# MCU025A_Connectors.net
KiCad netlist of a schematic drawn in Altium Designer
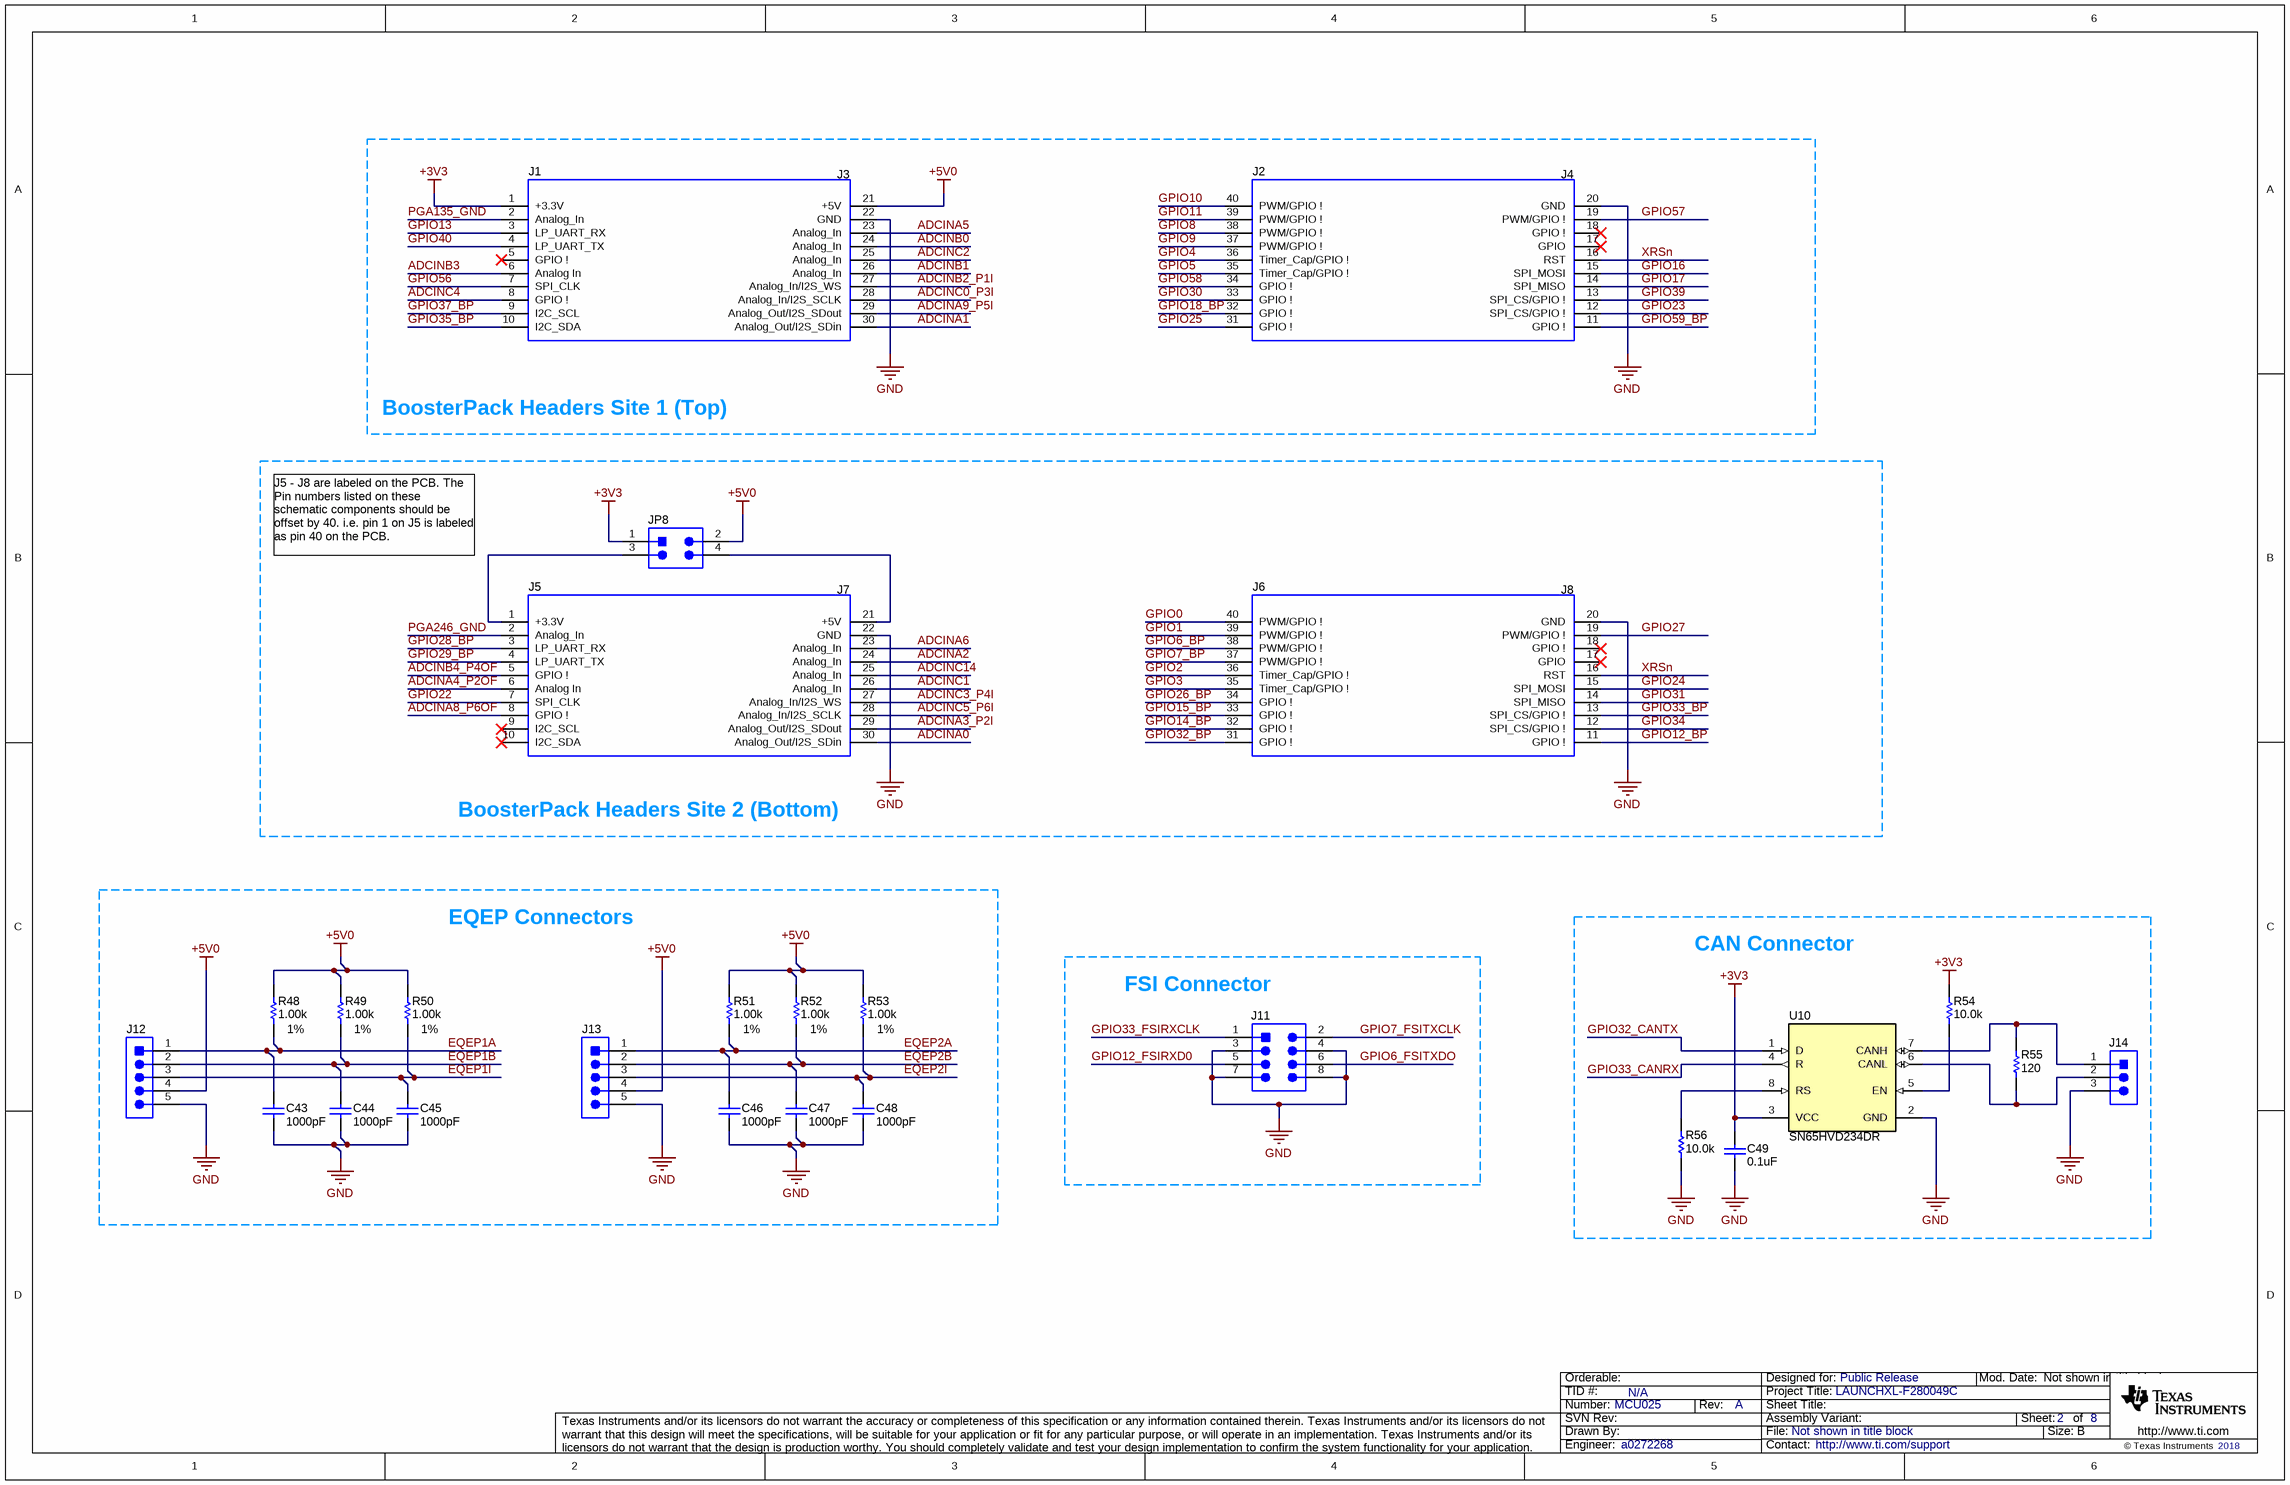
[diagram p0: MCU025A_Connectors.SchDoc]

(export (version "E")
  (design (tool "Eeschema 10.0.6"))
  (components
    (comp (ref "C43")
      (value "GRM155R71H102KA01D")
      (footprint "0402")
      (description "CAP, CERM, 1000 pF, 50 V, +/- 10%, X7R, 0402")
      (fields
        (field (name "VALUEDISPLAYED") "1000pF")
        (field (name "MANUFACTURER") "MuRata")
        (field (name "PUBLISHER") "Texas Instruments")
      )
      (libsource (lib "Altium Vault - TI") (part "Capacitor"))
    )
    (comp (ref "C44")
      (value "GRM155R71H102KA01D")
      (footprint "0402")
      (description "CAP, CERM, 1000 pF, 50 V, +/- 10%, X7R, 0402")
      (fields
        (field (name "VALUEDISPLAYED") "1000pF")
        (field (name "MANUFACTURER") "MuRata")
        (field (name "PUBLISHER") "Texas Instruments")
      )
      (libsource (lib "Altium Vault - TI") (part "Capacitor"))
    )
    (comp (ref "C45")
      (value "GRM155R71H102KA01D")
      (footprint "0402")
      (description "CAP, CERM, 1000 pF, 50 V, +/- 10%, X7R, 0402")
      (fields
        (field (name "VALUEDISPLAYED") "1000pF")
        (field (name "MANUFACTURER") "MuRata")
        (field (name "PUBLISHER") "Texas Instruments")
      )
      (libsource (lib "Altium Vault - TI") (part "Capacitor"))
    )
    (comp (ref "C46")
      (value "GRM155R71H102KA01D")
      (footprint "0402")
      (description "CAP, CERM, 1000 pF, 50 V, +/- 10%, X7R, 0402")
      (fields
        (field (name "VALUEDISPLAYED") "1000pF")
        (field (name "MANUFACTURER") "MuRata")
        (field (name "PUBLISHER") "Texas Instruments")
      )
      (libsource (lib "Altium Vault - TI") (part "Capacitor"))
    )
    (comp (ref "C47")
      (value "GRM155R71H102KA01D")
      (footprint "0402")
      (description "CAP, CERM, 1000 pF, 50 V, +/- 10%, X7R, 0402")
      (fields
        (field (name "VALUEDISPLAYED") "1000pF")
        (field (name "MANUFACTURER") "MuRata")
        (field (name "PUBLISHER") "Texas Instruments")
      )
      (libsource (lib "Altium Vault - TI") (part "Capacitor"))
    )
    (comp (ref "C48")
      (value "GRM155R71H102KA01D")
      (footprint "0402")
      (description "CAP, CERM, 1000 pF, 50 V, +/- 10%, X7R, 0402")
      (fields
        (field (name "VALUEDISPLAYED") "1000pF")
        (field (name "MANUFACTURER") "MuRata")
        (field (name "PUBLISHER") "Texas Instruments")
      )
      (libsource (lib "Altium Vault - TI") (part "Capacitor"))
    )
    (comp (ref "C49")
      (value "GRM155R71A104KA01D")
      (footprint "0402")
      (description "CAP, CERM, 0.1 uF, 10 V, +/- 10%, X7R, 0402")
      (fields
        (field (name "VALUEDISPLAYED") "0.1uF")
        (field (name "MANUFACTURER") "MuRata")
        (field (name "PUBLISHER") "Texas Instruments")
      )
      (libsource (lib "Altium Vault - TI") (part "Capacitor"))
    )
    (comp (ref "J1")
      (value "SSQ-110-03-T-D")
      (footprint "BoosterPack_40pin_J1J3")
      (description "Receptacle, 2.54mm, 10x2, Tin, TH")
      (fields (field (name "MANUFACTURER") "Samtec") (field (name "ALTERNATE PARTNUMBER") "CRD-081413-A-G"))
      (libsource (lib "Altium Vault - TI") (part "BoosterPack_40pin_J1J3"))
    )
    (comp (ref "J2")
      (value "SSQ-110-03-T-D")
      (footprint "BoosterPack_40pin_J2J4")
      (description "Receptacle, 2.54mm, 10x2, Tin, TH")
      (fields (field (name "MANUFACTURER") "Samtec") (field (name "ALTERNATE PARTNUMBER") "CRD-081413-A-G"))
      (libsource (lib "Altium Vault - TI") (part "BoosterPack_40pin_J2J4"))
    )
    (comp (ref "J5")
      (value "SSQ-110-03-T-D")
      (footprint "BoosterPack_40pin_J1J3")
      (description "Receptacle, 2.54mm, 10x2, Tin, TH")
      (fields (field (name "MANUFACTURER") "Samtec") (field (name "ALTERNATE PARTNUMBER") "CRD-081413-A-G"))
      (libsource (lib "Altium Vault - TI") (part "BoosterPack_40pin_J1J3"))
    )
    (comp (ref "J6")
      (value "SSQ-110-03-T-D")
      (footprint "BoosterPack_40pin_J2J4")
      (description "Receptacle, 2.54mm, 10x2, Tin, TH")
      (fields (field (name "MANUFACTURER") "Samtec") (field (name "ALTERNATE PARTNUMBER") "CRD-081413-A-G"))
      (libsource (lib "Altium Vault - TI") (part "BoosterPack_40pin_J2J4"))
    )
    (comp (ref "J11")
      (value "TSW-104-07-G-D")
      (footprint "TSW-104-07-G-D")
      (description "Header, 100mil, 4x2, Gold, TH")
      (fields (field (name "MANUFACTURER") "Samtec") (field (name "PUBLISHER") "Texas Instruments"))
      (libsource (lib "Altium Vault - TI") (part "CMP-0075408-1"))
    )
    (comp (ref "J12")
      (value "TSW-105-07-G-S")
      (footprint "TSW-105-07-X-S")
      (description "Header, 100mil, 5x1, Gold, TH")
      (fields (field (name "MANUFACTURER") "Samtec") (field (name "PUBLISHER") "Texas Instruments"))
      (libsource (lib "Altium Vault - TI") (part "Header_5x1"))
    )
    (comp (ref "J13")
      (value "TSW-105-07-G-S")
      (footprint "TSW-105-07-X-S")
      (description "Header, 100mil, 5x1, Gold, TH")
      (fields (field (name "MANUFACTURER") "Samtec") (field (name "PUBLISHER") "Texas Instruments"))
      (libsource (lib "Altium Vault - TI") (part "Header_5x1"))
    )
    (comp (ref "J14")
      (value "61300311121")
      (footprint "WURTH_61300311121")
      (description "Header, 2.54 mm, 3x1, Gold, TH")
      (fields (field (name "MANUFACTURER") "Wurth Elektronik") (field (name "PUBLISHER") "Texas Instruments"))
      (libsource (lib "Altium Vault - TI") (part "CMP-0054796-1"))
    )
    (comp (ref "JP8")
      (value "TSW-102-07-G-D")
      (footprint "TSW-102-07-G-D")
      (description "Header, 100mil, 2x2, Gold, TH")
      (fields (field (name "MANUFACTURER") "Samtec") (field (name "PUBLISHER") "Texas Instruments"))
      (libsource (lib "Altium Vault - TI") (part "Header_2x2"))
    )
    (comp (ref "R48")
      (value "CRCW04021K00FKED")
      (footprint "0402")
      (description "RES, 1.00 k, 1%, 0.063 W, AEC-Q200 Grade 0, 0402")
      (fields
        (field (name "VALUEDISPLAYED") "1.00k")
        (field (name "MANUFACTURER") "Vishay-Dale")
        (field (name "VALUE1") "1%")
      )
      (libsource (lib "Altium Vault - TI") (part "Resistor"))
    )
    (comp (ref "R49")
      (value "CRCW04021K00FKED")
      (footprint "0402")
      (description "RES, 1.00 k, 1%, 0.063 W, AEC-Q200 Grade 0, 0402")
      (fields
        (field (name "VALUEDISPLAYED") "1.00k")
        (field (name "MANUFACTURER") "Vishay-Dale")
        (field (name "VALUE1") "1%")
      )
      (libsource (lib "Altium Vault - TI") (part "Resistor"))
    )
    (comp (ref "R50")
      (value "CRCW04021K00FKED")
      (footprint "0402")
      (description "RES, 1.00 k, 1%, 0.063 W, AEC-Q200 Grade 0, 0402")
      (fields
        (field (name "VALUEDISPLAYED") "1.00k")
        (field (name "MANUFACTURER") "Vishay-Dale")
        (field (name "VALUE1") "1%")
      )
      (libsource (lib "Altium Vault - TI") (part "Resistor"))
    )
    (comp (ref "R51")
      (value "CRCW04021K00FKED")
      (footprint "0402")
      (description "RES, 1.00 k, 1%, 0.063 W, AEC-Q200 Grade 0, 0402")
      (fields
        (field (name "VALUEDISPLAYED") "1.00k")
        (field (name "MANUFACTURER") "Vishay-Dale")
        (field (name "VALUE1") "1%")
      )
      (libsource (lib "Altium Vault - TI") (part "Resistor"))
    )
    (comp (ref "R52")
      (value "CRCW04021K00FKED")
      (footprint "0402")
      (description "RES, 1.00 k, 1%, 0.063 W, AEC-Q200 Grade 0, 0402")
      (fields
        (field (name "VALUEDISPLAYED") "1.00k")
        (field (name "MANUFACTURER") "Vishay-Dale")
        (field (name "VALUE1") "1%")
      )
      (libsource (lib "Altium Vault - TI") (part "Resistor"))
    )
    (comp (ref "R53")
      (value "CRCW04021K00FKED")
      (footprint "0402")
      (description "RES, 1.00 k, 1%, 0.063 W, AEC-Q200 Grade 0, 0402")
      (fields
        (field (name "VALUEDISPLAYED") "1.00k")
        (field (name "MANUFACTURER") "Vishay-Dale")
        (field (name "VALUE1") "1%")
      )
      (libsource (lib "Altium Vault - TI") (part "Resistor"))
    )
    (comp (ref "R54")
      (value "CRCW040210K0FKED")
      (footprint "0402")
      (description "RES, 10.0 k, 1%, 0.063 W, AEC-Q200 Grade 0, 0402")
      (fields (field (name "VALUEDISPLAYED") "10.0k") (field (name "MANUFACTURER") "Vishay-Dale"))
      (libsource (lib "Altium Vault - TI") (part "Resistor"))
    )
    (comp (ref "R55")
      (value "RC0603FR-07120RL")
      (footprint "0603")
      (description "RES, 120, 1%, 0.1 W, 0603")
      (fields
        (field (name "VALUEDISPLAYED") "120")
        (field (name "MANUFACTURER") "Yageo America")
        (field (name "PUBLISHER") "Texas Instruments")
      )
      (libsource (lib "Altium Vault - TI") (part "Resistor"))
    )
    (comp (ref "R56")
      (value "CRCW040210K0FKED")
      (footprint "0402")
      (description "RES, 10.0 k, 1%, 0.063 W, AEC-Q200 Grade 0, 0402")
      (fields (field (name "VALUEDISPLAYED") "10.0k") (field (name "MANUFACTURER") "Vishay-Dale"))
      (libsource (lib "Altium Vault - TI") (part "Resistor"))
    )
    (comp (ref "U10")
      (value "SN65HVD234DR")
      (footprint "D0008A_L")
      (fields (field (name "MANUFACTURER") "Texas Instruments"))
      (libsource (lib "Altium Vault - TI") (part "TI-SN65HVD234-SOIC_D-8"))
    )
  )
  (nets
    (net (code "1") (name "+3V3") (class "Default")
      (node (ref "C49") (pin "2") (pinfunction "2_2") (pintype "passive"))
      (node (ref "J1") (pin "1") (pinfunction "+3.3V_1") (pintype "power_in"))
      (node (ref "JP8") (pin "1") (pinfunction "1_1") (pintype "passive"))
      (node (ref "R54") (pin "2") (pinfunction "2_2") (pintype "passive"))
      (node (ref "U10") (pin "3") (pinfunction "VCC_3") (pintype "power_in"))
    )
    (net (code "2") (name "+5V0") (class "Default")
      (node (ref "J1") (pin "21") (pinfunction "+5V_21") (pintype "power_in"))
      (node (ref "J12") (pin "4") (pinfunction "4_4") (pintype "passive"))
      (node (ref "J13") (pin "4") (pinfunction "4_4") (pintype "passive"))
      (node (ref "JP8") (pin "2") (pinfunction "2_2") (pintype "passive"))
      (node (ref "R48") (pin "2") (pinfunction "2_2") (pintype "passive"))
      (node (ref "R49") (pin "2") (pinfunction "2_2") (pintype "passive"))
      (node (ref "R50") (pin "2") (pinfunction "2_2") (pintype "passive"))
      (node (ref "R51") (pin "2") (pinfunction "2_2") (pintype "passive"))
      (node (ref "R52") (pin "2") (pinfunction "2_2") (pintype "passive"))
      (node (ref "R53") (pin "2") (pinfunction "2_2") (pintype "passive"))
    )
    (net (code "3") (name "/ADCINA0") (class "Default")
      (node (ref "J5") (pin "30") (pinfunction "Analog_Out/I2S_SDin_30") (pintype "passive"))
    )
    (net (code "4") (name "/ADCINA1") (class "Default")
      (node (ref "J1") (pin "30") (pinfunction "Analog_Out/I2S_SDin_30") (pintype "passive"))
    )
    (net (code "5") (name "/ADCINA2") (class "Default")
      (node (ref "J5") (pin "24") (pinfunction "Analog_In_24") (pintype "passive"))
    )
    (net (code "6") (name "/ADCINA3_P2I") (class "Default")
      (node (ref "J5") (pin "29") (pinfunction "Analog_Out/I2S_SDout_29") (pintype "passive"))
    )
    (net (code "7") (name "/ADCINA4_P2OF") (class "Default")
      (node (ref "J5") (pin "6") (pinfunction "Analog_In_6") (pintype "passive"))
    )
    (net (code "8") (name "/ADCINA5") (class "Default")
      (node (ref "J1") (pin "23") (pinfunction "Analog_In_23") (pintype "passive"))
    )
    (net (code "9") (name "/ADCINA6") (class "Default")
      (node (ref "J5") (pin "23") (pinfunction "Analog_In_23") (pintype "passive"))
    )
    (net (code "10") (name "/ADCINA8_P6OF") (class "Default")
      (node (ref "J5") (pin "8") (pinfunction "GPIO_!_8") (pintype "passive"))
    )
    (net (code "11") (name "/ADCINA9_P5I") (class "Default")
      (node (ref "J1") (pin "29") (pinfunction "Analog_Out/I2S_SDout_29") (pintype "passive"))
    )
    (net (code "12") (name "/ADCINB0") (class "Default")
      (node (ref "J1") (pin "24") (pinfunction "Analog_In_24") (pintype "passive"))
    )
    (net (code "13") (name "/ADCINB1") (class "Default")
      (node (ref "J1") (pin "26") (pinfunction "Analog_In_26") (pintype "passive"))
    )
    (net (code "14") (name "/ADCINB2_P1I") (class "Default")
      (node (ref "J1") (pin "27") (pinfunction "Analog_In/I2S_WS_27") (pintype "passive"))
    )
    (net (code "15") (name "/ADCINB3") (class "Default")
      (node (ref "J1") (pin "6") (pinfunction "Analog_In_6") (pintype "passive"))
    )
    (net (code "16") (name "/ADCINB4_P4OF") (class "Default")
      (node (ref "J5") (pin "5") (pinfunction "GPIO_!_5") (pintype "passive"))
    )
    (net (code "17") (name "/ADCINC0_P3I") (class "Default")
      (node (ref "J1") (pin "28") (pinfunction "Analog_In/I2S_SCLK_28") (pintype "passive"))
    )
    (net (code "18") (name "/ADCINC1") (class "Default")
      (node (ref "J5") (pin "26") (pinfunction "Analog_In_26") (pintype "passive"))
    )
    (net (code "19") (name "/ADCINC2") (class "Default")
      (node (ref "J1") (pin "25") (pinfunction "Analog_In_25") (pintype "passive"))
    )
    (net (code "20") (name "/ADCINC3_P4I") (class "Default")
      (node (ref "J5") (pin "27") (pinfunction "Analog_In/I2S_WS_27") (pintype "passive"))
    )
    (net (code "21") (name "/ADCINC4") (class "Default")
      (node (ref "J1") (pin "8") (pinfunction "GPIO_!_8") (pintype "passive"))
    )
    (net (code "22") (name "/ADCINC5_P6I") (class "Default")
      (node (ref "J5") (pin "28") (pinfunction "Analog_In/I2S_SCLK_28") (pintype "passive"))
    )
    (net (code "23") (name "/ADCINC14") (class "Default")
      (node (ref "J5") (pin "25") (pinfunction "Analog_In_25") (pintype "passive"))
    )
    (net (code "24") (name "/EQEP1A") (class "Default")
      (node (ref "C43") (pin "1") (pinfunction "1_1") (pintype "passive"))
      (node (ref "J12") (pin "1") (pinfunction "1_1") (pintype "passive"))
      (node (ref "R48") (pin "1") (pinfunction "1_1") (pintype "passive"))
    )
    (net (code "25") (name "/EQEP1B") (class "Default")
      (node (ref "C44") (pin "1") (pinfunction "1_1") (pintype "passive"))
      (node (ref "J12") (pin "2") (pinfunction "2_2") (pintype "passive"))
      (node (ref "R49") (pin "1") (pinfunction "1_1") (pintype "passive"))
    )
    (net (code "26") (name "/EQEP1I") (class "Default")
      (node (ref "C45") (pin "1") (pinfunction "1_1") (pintype "passive"))
      (node (ref "J12") (pin "3") (pinfunction "3_3") (pintype "passive"))
      (node (ref "R50") (pin "1") (pinfunction "1_1") (pintype "passive"))
    )
    (net (code "27") (name "/EQEP2A") (class "Default")
      (node (ref "C46") (pin "1") (pinfunction "1_1") (pintype "passive"))
      (node (ref "J13") (pin "1") (pinfunction "1_1") (pintype "passive"))
      (node (ref "R51") (pin "1") (pinfunction "1_1") (pintype "passive"))
    )
    (net (code "28") (name "/EQEP2B") (class "Default")
      (node (ref "C47") (pin "1") (pinfunction "1_1") (pintype "passive"))
      (node (ref "J13") (pin "2") (pinfunction "2_2") (pintype "passive"))
      (node (ref "R52") (pin "1") (pinfunction "1_1") (pintype "passive"))
    )
    (net (code "29") (name "/EQEP2I") (class "Default")
      (node (ref "C48") (pin "1") (pinfunction "1_1") (pintype "passive"))
      (node (ref "J13") (pin "3") (pinfunction "3_3") (pintype "passive"))
      (node (ref "R53") (pin "1") (pinfunction "1_1") (pintype "passive"))
    )
    (net (code "30") (name "/GPIO0") (class "Default")
      (node (ref "J6") (pin "40") (pinfunction "PWM/GPIO_!_40") (pintype "passive"))
    )
    (net (code "31") (name "/GPIO1") (class "Default")
      (node (ref "J6") (pin "39") (pinfunction "PWM/GPIO_!_39") (pintype "passive"))
    )
    (net (code "32") (name "/GPIO2") (class "Default")
      (node (ref "J6") (pin "36") (pinfunction "Timer_Cap/GPIO_!_36") (pintype "passive"))
    )
    (net (code "33") (name "/GPIO3") (class "Default")
      (node (ref "J6") (pin "35") (pinfunction "Timer_Cap/GPIO_!_35") (pintype "passive"))
    )
    (net (code "34") (name "/GPIO4") (class "Default")
      (node (ref "J2") (pin "36") (pinfunction "Timer_Cap/GPIO_!_36") (pintype "passive"))
    )
    (net (code "35") (name "/GPIO5") (class "Default")
      (node (ref "J2") (pin "35") (pinfunction "Timer_Cap/GPIO_!_35") (pintype "passive"))
    )
    (net (code "36") (name "/GPIO6_BP") (class "Default")
      (node (ref "J6") (pin "38") (pinfunction "PWM/GPIO_!_38") (pintype "passive"))
    )
    (net (code "37") (name "/GPIO6_FSITXDO") (class "Default")
      (node (ref "J11") (pin "6") (pinfunction "6_6") (pintype "passive"))
    )
    (net (code "38") (name "/GPIO7_BP") (class "Default")
      (node (ref "J6") (pin "37") (pinfunction "PWM/GPIO_!_37") (pintype "passive"))
    )
    (net (code "39") (name "/GPIO7_FSITXCLK") (class "Default")
      (node (ref "J11") (pin "2") (pinfunction "2_2") (pintype "passive"))
    )
    (net (code "40") (name "/GPIO8") (class "Default")
      (node (ref "J2") (pin "38") (pinfunction "PWM/GPIO_!_38") (pintype "passive"))
    )
    (net (code "41") (name "/GPIO9") (class "Default")
      (node (ref "J2") (pin "37") (pinfunction "PWM/GPIO_!_37") (pintype "passive"))
    )
    (net (code "42") (name "/GPIO10") (class "Default")
      (node (ref "J2") (pin "40") (pinfunction "PWM/GPIO_!_40") (pintype "passive"))
    )
    (net (code "43") (name "/GPIO11") (class "Default")
      (node (ref "J2") (pin "39") (pinfunction "PWM/GPIO_!_39") (pintype "passive"))
    )
    (net (code "44") (name "/GPIO12_BP") (class "Default")
      (node (ref "J6") (pin "11") (pinfunction "GPIO_!_11") (pintype "passive"))
    )
    (net (code "45") (name "/GPIO12_FSIRXD0") (class "Default")
      (node (ref "J11") (pin "5") (pinfunction "5_5") (pintype "passive"))
    )
    (net (code "46") (name "/GPIO13") (class "Default")
      (node (ref "J1") (pin "3") (pinfunction "LP_UART_RX_3") (pintype "passive"))
    )
    (net (code "47") (name "/GPIO14_BP") (class "Default")
      (node (ref "J6") (pin "32") (pinfunction "GPIO_!_32") (pintype "passive"))
    )
    (net (code "48") (name "/GPIO15_BP") (class "Default")
      (node (ref "J6") (pin "33") (pinfunction "GPIO_!_33") (pintype "passive"))
    )
    (net (code "49") (name "/GPIO16") (class "Default")
      (node (ref "J2") (pin "15") (pinfunction "SPI_MOSI_15") (pintype "passive"))
    )
    (net (code "50") (name "/GPIO17") (class "Default")
      (node (ref "J2") (pin "14") (pinfunction "SPI_MISO_14") (pintype "passive"))
    )
    (net (code "51") (name "/GPIO18_BP") (class "Default")
      (node (ref "J2") (pin "32") (pinfunction "GPIO_!_32") (pintype "passive"))
    )
    (net (code "52") (name "/GPIO22") (class "Default")
      (node (ref "J5") (pin "7") (pinfunction "SPI_CLK_7") (pintype "passive"))
    )
    (net (code "53") (name "/GPIO23") (class "Default")
      (node (ref "J2") (pin "12") (pinfunction "SPI_CS/GPIO_!_12") (pintype "passive"))
    )
    (net (code "54") (name "/GPIO24") (class "Default")
      (node (ref "J6") (pin "15") (pinfunction "SPI_MOSI_15") (pintype "passive"))
    )
    (net (code "55") (name "/GPIO25") (class "Default")
      (node (ref "J2") (pin "31") (pinfunction "GPIO_!_31") (pintype "passive"))
    )
    (net (code "56") (name "/GPIO26_BP") (class "Default")
      (node (ref "J6") (pin "34") (pinfunction "GPIO_!_34") (pintype "passive"))
    )
    (net (code "57") (name "/GPIO27") (class "Default")
      (node (ref "J6") (pin "19") (pinfunction "PWM/GPIO_!_19") (pintype "passive"))
    )
    (net (code "58") (name "/GPIO28_BP") (class "Default")
      (node (ref "J5") (pin "3") (pinfunction "LP_UART_RX_3") (pintype "passive"))
    )
    (net (code "59") (name "/GPIO29_BP") (class "Default")
      (node (ref "J5") (pin "4") (pinfunction "LP_UART_TX_4") (pintype "passive"))
    )
    (net (code "60") (name "/GPIO30") (class "Default")
      (node (ref "J2") (pin "33") (pinfunction "GPIO_!_33") (pintype "passive"))
    )
    (net (code "61") (name "/GPIO31") (class "Default")
      (node (ref "J6") (pin "14") (pinfunction "SPI_MISO_14") (pintype "passive"))
    )
    (net (code "62") (name "/GPIO32_BP") (class "Default")
      (node (ref "J6") (pin "31") (pinfunction "GPIO_!_31") (pintype "passive"))
    )
    (net (code "63") (name "/GPIO32_CANTX") (class "Default")
      (node (ref "U10") (pin "1") (pinfunction "D_1") (pintype "input"))
    )
    (net (code "64") (name "/GPIO33_BP") (class "Default")
      (node (ref "J6") (pin "13") (pinfunction "SPI_CS/GPIO_!_13") (pintype "passive"))
    )
    (net (code "65") (name "/GPIO33_CANRX") (class "Default")
      (node (ref "U10") (pin "4") (pinfunction "R_4") (pintype "output"))
    )
    (net (code "66") (name "/GPIO33_FSIRXCLK") (class "Default")
      (node (ref "J11") (pin "1") (pinfunction "1_1") (pintype "passive"))
    )
    (net (code "67") (name "/GPIO34") (class "Default")
      (node (ref "J6") (pin "12") (pinfunction "SPI_CS/GPIO_!_12") (pintype "passive"))
    )
    (net (code "68") (name "/GPIO35_BP") (class "Default")
      (node (ref "J1") (pin "10") (pinfunction "I2C_SDA_10") (pintype "passive"))
    )
    (net (code "69") (name "/GPIO37_BP") (class "Default")
      (node (ref "J1") (pin "9") (pinfunction "I2C_SCL_9") (pintype "passive"))
    )
    (net (code "70") (name "/GPIO39") (class "Default")
      (node (ref "J2") (pin "13") (pinfunction "SPI_CS/GPIO_!_13") (pintype "passive"))
    )
    (net (code "71") (name "/GPIO40") (class "Default")
      (node (ref "J1") (pin "4") (pinfunction "LP_UART_TX_4") (pintype "passive"))
    )
    (net (code "72") (name "/GPIO56") (class "Default")
      (node (ref "J1") (pin "7") (pinfunction "SPI_CLK_7") (pintype "passive"))
    )
    (net (code "73") (name "/GPIO57") (class "Default")
      (node (ref "J2") (pin "19") (pinfunction "PWM/GPIO_!_19") (pintype "passive"))
    )
    (net (code "74") (name "/GPIO58") (class "Default")
      (node (ref "J2") (pin "34") (pinfunction "GPIO_!_34") (pintype "passive"))
    )
    (net (code "75") (name "/GPIO59_BP") (class "Default")
      (node (ref "J2") (pin "11") (pinfunction "GPIO_!_11") (pintype "passive"))
    )
    (net (code "76") (name "/PGA135_GND") (class "Default")
      (node (ref "J1") (pin "2") (pinfunction "Analog_In_2") (pintype "passive"))
    )
    (net (code "77") (name "/PGA246_GND") (class "Default")
      (node (ref "J5") (pin "2") (pinfunction "Analog_In_2") (pintype "passive"))
    )
    (net (code "78") (name "/XRSn") (class "Default")
      (node (ref "J2") (pin "16") (pinfunction "RST_16") (pintype "passive"))
      (node (ref "J6") (pin "16") (pinfunction "RST_16") (pintype "passive"))
    )
    (net (code "79") (name "GND") (class "Default")
      (node (ref "C43") (pin "2") (pinfunction "2_2") (pintype "passive"))
      (node (ref "C44") (pin "2") (pinfunction "2_2") (pintype "passive"))
      (node (ref "C45") (pin "2") (pinfunction "2_2") (pintype "passive"))
      (node (ref "C46") (pin "2") (pinfunction "2_2") (pintype "passive"))
      (node (ref "C47") (pin "2") (pinfunction "2_2") (pintype "passive"))
      (node (ref "C48") (pin "2") (pinfunction "2_2") (pintype "passive"))
      (node (ref "C49") (pin "1") (pinfunction "1_1") (pintype "passive"))
      (node (ref "J1") (pin "22") (pinfunction "GND_22") (pintype "power_in"))
      (node (ref "J11") (pin "3") (pinfunction "3_3") (pintype "passive"))
      (node (ref "J11") (pin "4") (pinfunction "4_4") (pintype "passive"))
      (node (ref "J11") (pin "7") (pinfunction "7_7") (pintype "passive"))
      (node (ref "J11") (pin "8") (pinfunction "8_8") (pintype "passive"))
      (node (ref "J12") (pin "5") (pinfunction "5_5") (pintype "passive"))
      (node (ref "J13") (pin "5") (pinfunction "5_5") (pintype "passive"))
      (node (ref "J14") (pin "3") (pinfunction "3_3") (pintype "passive"))
      (node (ref "J2") (pin "20") (pinfunction "GND_20") (pintype "power_in"))
      (node (ref "J5") (pin "22") (pinfunction "GND_22") (pintype "power_in"))
      (node (ref "J6") (pin "20") (pinfunction "GND_20") (pintype "power_in"))
      (node (ref "R56") (pin "1") (pinfunction "1_1") (pintype "passive"))
      (node (ref "U10") (pin "2") (pinfunction "GND_2") (pintype "power_in"))
    )
    (net (code "80") (name "Net-(J5-+3.3V)") (class "Default")
      (node (ref "J5") (pin "1") (pinfunction "+3.3V_1") (pintype "power_in"))
      (node (ref "JP8") (pin "3") (pinfunction "3_3") (pintype "passive"))
    )
    (net (code "81") (name "Net-(J5-+5V)") (class "Default")
      (node (ref "J5") (pin "21") (pinfunction "+5V_21") (pintype "power_in"))
      (node (ref "JP8") (pin "4") (pinfunction "4_4") (pintype "passive"))
    )
    (net (code "82") (name "Net-(U10-CANH)") (class "Default")
      (node (ref "J14") (pin "1") (pinfunction "1_1") (pintype "passive"))
      (node (ref "R55") (pin "2") (pinfunction "2_2") (pintype "passive"))
      (node (ref "U10") (pin "7") (pinfunction "CANH_7") (pintype "bidirectional"))
    )
    (net (code "83") (name "Net-(U10-CANL)") (class "Default")
      (node (ref "J14") (pin "2") (pinfunction "2_2") (pintype "passive"))
      (node (ref "R55") (pin "1") (pinfunction "1_1") (pintype "passive"))
      (node (ref "U10") (pin "6") (pinfunction "CANL_6") (pintype "bidirectional"))
    )
    (net (code "84") (name "Net-(U10-EN)") (class "Default")
      (node (ref "R54") (pin "1") (pinfunction "1_1") (pintype "passive"))
      (node (ref "U10") (pin "5") (pinfunction "EN_5") (pintype "input"))
    )
    (net (code "85") (name "Net-(U10-RS)") (class "Default")
      (node (ref "R56") (pin "2") (pinfunction "2_2") (pintype "passive"))
      (node (ref "U10") (pin "8") (pinfunction "RS_8") (pintype "input"))
    )
    (net (code "86") (name "unconnected-(J1-GPIO_!-Pad5)") (class "Default")
      (node (ref "J1") (pin "5") (pinfunction "GPIO_!_5") (pintype "passive+no_connect"))
    )
    (net (code "87") (name "unconnected-(J2-GPIO-Pad17)") (class "Default")
      (node (ref "J2") (pin "17") (pinfunction "GPIO_17") (pintype "passive+no_connect"))
    )
    (net (code "88") (name "unconnected-(J2-GPIO_!-Pad18)") (class "Default")
      (node (ref "J2") (pin "18") (pinfunction "GPIO_!_18") (pintype "passive+no_connect"))
    )
    (net (code "89") (name "unconnected-(J5-I2C_SCL-Pad9)") (class "Default")
      (node (ref "J5") (pin "9") (pinfunction "I2C_SCL_9") (pintype "passive+no_connect"))
    )
    (net (code "90") (name "unconnected-(J5-I2C_SDA-Pad10)") (class "Default")
      (node (ref "J5") (pin "10") (pinfunction "I2C_SDA_10") (pintype "passive+no_connect"))
    )
    (net (code "91") (name "unconnected-(J6-GPIO-Pad17)") (class "Default")
      (node (ref "J6") (pin "17") (pinfunction "GPIO_17") (pintype "passive+no_connect"))
    )
    (net (code "92") (name "unconnected-(J6-GPIO_!-Pad18)") (class "Default")
      (node (ref "J6") (pin "18") (pinfunction "GPIO_!_18") (pintype "passive+no_connect"))
    )
  )
)
